# denary-cell-v1.net
KiCad netlist of a schematic drawn in EAGLE
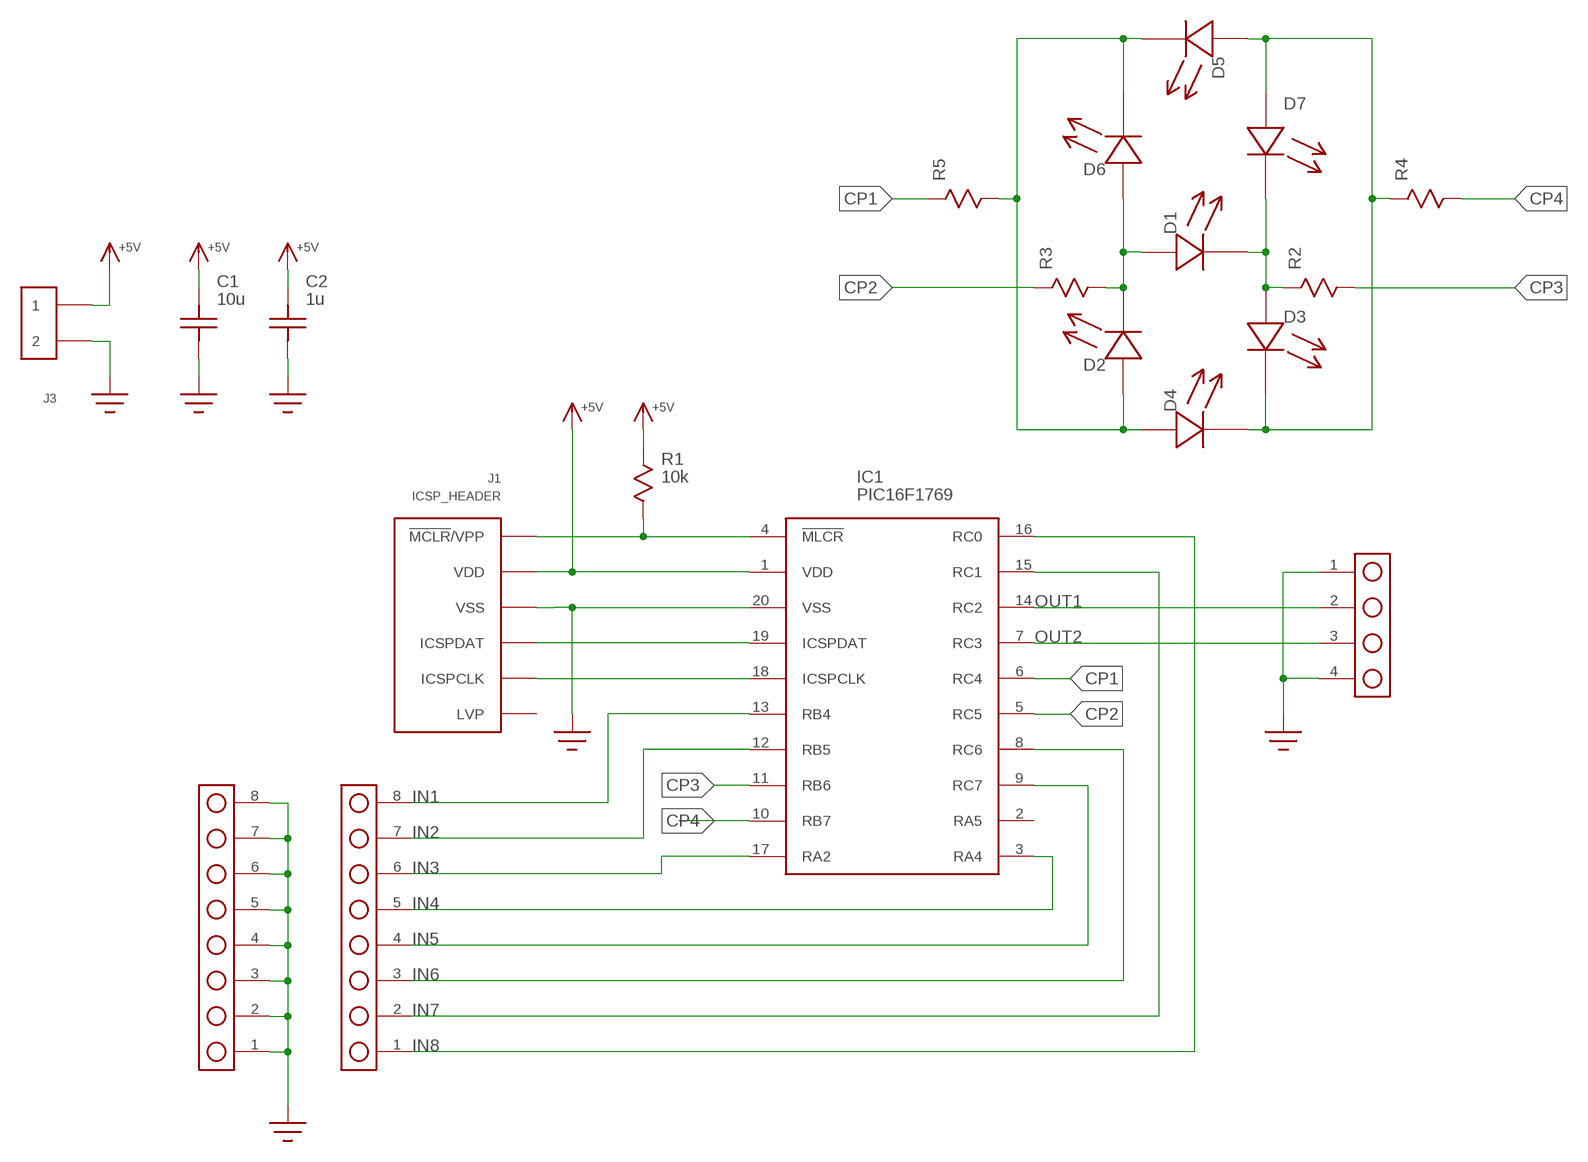
[diagram p0: schematic, sheet 1]

(export (version "E")
  (design (tool "Eeschema 10.0.6"))
  (components
    (comp (ref "C1")
      (value "10u")
      (footprint "eagle-import:1206")
      (libsource (lib "eagle-import") (part "C1206"))
    )
    (comp (ref "C2")
      (value "1u")
      (footprint "eagle-import:C0603")
      (libsource (lib "eagle-import") (part "C0603"))
    )
    (comp (ref "D1")
      (value "LED")
      (footprint "eagle-import:LED_0603")
      (libsource (lib "eagle-import") (part "LED"))
    )
    (comp (ref "D2")
      (value "LED")
      (footprint "eagle-import:LED_0603")
      (libsource (lib "eagle-import") (part "LED"))
    )
    (comp (ref "D3")
      (value "LED")
      (footprint "eagle-import:LED_0603")
      (libsource (lib "eagle-import") (part "LED"))
    )
    (comp (ref "D4")
      (value "LED")
      (footprint "eagle-import:LED_0603")
      (libsource (lib "eagle-import") (part "LED"))
    )
    (comp (ref "D5")
      (value "LED")
      (footprint "eagle-import:LED_0603")
      (libsource (lib "eagle-import") (part "LED"))
    )
    (comp (ref "D6")
      (value "LED")
      (footprint "eagle-import:LED_0603")
      (libsource (lib "eagle-import") (part "LED"))
    )
    (comp (ref "D7")
      (value "LED")
      (footprint "eagle-import:LED_0603")
      (libsource (lib "eagle-import") (part "LED"))
    )
    (comp (ref "IC1")
      (value "PIC16F1769")
      (footprint "eagle-import:SOIC-20W")
      (libsource (lib "eagle-import") (part "PIC16F1769"))
    )
    (comp (ref "J1")
      (value "ICSP_HEADER")
      (footprint "eagle-import:HEADER_6PIN")
      (libsource (lib "eagle-import") (part "ICSP_HEADER"))
    )
    (comp (ref "J2")
      (value "HEADER_4PIN")
      (footprint "eagle-import:HEADER_4PIN")
      (libsource (lib "eagle-import") (part "HEADER_4PIN"))
    )
    (comp (ref "J3")
      (value "HEADER_2PIN")
      (footprint "eagle-import:HEADER_2PIN")
      (libsource (lib "eagle-import") (part "HEADER_2PIN"))
    )
    (comp (ref "J4")
      (value "HEADER_8PIN")
      (footprint "eagle-import:HEADER_8_PIN")
      (libsource (lib "eagle-import") (part "HEADER_8PIN"))
    )
    (comp (ref "J5")
      (value "HEADER_8PIN")
      (footprint "eagle-import:HEADER_8_PIN")
      (libsource (lib "eagle-import") (part "HEADER_8PIN"))
    )
    (comp (ref "R1")
      (value "10k")
      (footprint "eagle-import:R0603")
      (libsource (lib "eagle-import") (part "R0603"))
    )
    (comp (ref "R2")
      (value "R0603")
      (footprint "eagle-import:R0603")
      (libsource (lib "eagle-import") (part "R0603"))
    )
    (comp (ref "R3")
      (value "R0603")
      (footprint "eagle-import:R0603")
      (libsource (lib "eagle-import") (part "R0603"))
    )
    (comp (ref "R4")
      (value "R0603")
      (footprint "eagle-import:R0603")
      (libsource (lib "eagle-import") (part "R0603"))
    )
    (comp (ref "R5")
      (value "R0603")
      (footprint "eagle-import:R0603")
      (libsource (lib "eagle-import") (part "R0603"))
    )
  )
  (nets
    (net (code "1") (name "+5V") (class "Default")
      (node (ref "C1") (pin "P$2") (pinfunction "P$2_P$2") (pintype "bidirectional"))
      (node (ref "C2") (pin "P$2") (pinfunction "P$2_P$2") (pintype "bidirectional"))
      (node (ref "IC1") (pin "1") (pinfunction "VDD_1") (pintype "bidirectional"))
      (node (ref "J1") (pin "2") (pinfunction "VDD_2") (pintype "bidirectional"))
      (node (ref "J3") (pin "1") (pinfunction "1_1") (pintype "bidirectional"))
      (node (ref "R1") (pin "P$1") (pinfunction "P$3_P$1") (pintype "bidirectional"))
    )
    (net (code "2") (name "/IN1") (class "Default")
      (node (ref "IC1") (pin "13") (pinfunction "RB4_13") (pintype "bidirectional"))
      (node (ref "J4") (pin "8") (pinfunction "8_8") (pintype "bidirectional"))
    )
    (net (code "3") (name "/IN2") (class "Default")
      (node (ref "IC1") (pin "12") (pinfunction "RB5_12") (pintype "bidirectional"))
      (node (ref "J4") (pin "7") (pinfunction "7_7") (pintype "bidirectional"))
    )
    (net (code "4") (name "/IN3") (class "Default")
      (node (ref "IC1") (pin "17") (pinfunction "RA2_17") (pintype "bidirectional"))
      (node (ref "J4") (pin "6") (pinfunction "6_6") (pintype "bidirectional"))
    )
    (net (code "5") (name "/IN4") (class "Default")
      (node (ref "IC1") (pin "3") (pinfunction "RA4_3") (pintype "bidirectional"))
      (node (ref "J4") (pin "5") (pinfunction "5_5") (pintype "bidirectional"))
    )
    (net (code "6") (name "/IN5") (class "Default")
      (node (ref "IC1") (pin "9") (pinfunction "RC7_9") (pintype "bidirectional"))
      (node (ref "J4") (pin "4") (pinfunction "4_4") (pintype "bidirectional"))
    )
    (net (code "7") (name "/IN6") (class "Default")
      (node (ref "IC1") (pin "8") (pinfunction "RC6_8") (pintype "bidirectional"))
      (node (ref "J4") (pin "3") (pinfunction "3_3") (pintype "bidirectional"))
    )
    (net (code "8") (name "/IN7") (class "Default")
      (node (ref "IC1") (pin "15") (pinfunction "RC1_15") (pintype "bidirectional"))
      (node (ref "J4") (pin "2") (pinfunction "2_2") (pintype "bidirectional"))
    )
    (net (code "9") (name "/IN8") (class "Default")
      (node (ref "IC1") (pin "16") (pinfunction "RC0_16") (pintype "bidirectional"))
      (node (ref "J4") (pin "1") (pinfunction "1_1") (pintype "bidirectional"))
    )
    (net (code "10") (name "/OUT1") (class "Default")
      (node (ref "IC1") (pin "14") (pinfunction "RC2_14") (pintype "bidirectional"))
      (node (ref "J2") (pin "2") (pinfunction "2_2") (pintype "bidirectional"))
    )
    (net (code "11") (name "/OUT2") (class "Default")
      (node (ref "IC1") (pin "7") (pinfunction "RC3_7") (pintype "bidirectional"))
      (node (ref "J2") (pin "3") (pinfunction "3_3") (pintype "bidirectional"))
    )
    (net (code "12") (name "CP1") (class "Default")
      (node (ref "IC1") (pin "6") (pinfunction "RC4_6") (pintype "bidirectional"))
      (node (ref "R5") (pin "P$1") (pinfunction "P$3_P$1") (pintype "bidirectional"))
    )
    (net (code "13") (name "CP2") (class "Default")
      (node (ref "IC1") (pin "5") (pinfunction "RC5_5") (pintype "bidirectional"))
      (node (ref "R3") (pin "P$1") (pinfunction "P$3_P$1") (pintype "bidirectional"))
    )
    (net (code "14") (name "CP3") (class "Default")
      (node (ref "IC1") (pin "11") (pinfunction "RB6_11") (pintype "bidirectional"))
      (node (ref "R2") (pin "P$2") (pinfunction "P$4_P$2") (pintype "bidirectional"))
    )
    (net (code "15") (name "CP4") (class "Default")
      (node (ref "IC1") (pin "10") (pinfunction "RB7_10") (pintype "bidirectional"))
      (node (ref "R4") (pin "P$2") (pinfunction "P$4_P$2") (pintype "bidirectional"))
    )
    (net (code "16") (name "GND") (class "Default")
      (node (ref "C1") (pin "P$1") (pinfunction "P$1_P$1") (pintype "bidirectional"))
      (node (ref "C2") (pin "P$1") (pinfunction "P$1_P$1") (pintype "bidirectional"))
      (node (ref "IC1") (pin "20") (pinfunction "VSS_20") (pintype "bidirectional"))
      (node (ref "J1") (pin "3") (pinfunction "VSS_3") (pintype "bidirectional"))
      (node (ref "J2") (pin "1") (pinfunction "1_1") (pintype "bidirectional"))
      (node (ref "J2") (pin "4") (pinfunction "4_4") (pintype "bidirectional"))
      (node (ref "J3") (pin "2") (pinfunction "2_2") (pintype "bidirectional"))
      (node (ref "J5") (pin "1") (pinfunction "1_1") (pintype "bidirectional"))
      (node (ref "J5") (pin "2") (pinfunction "2_2") (pintype "bidirectional"))
      (node (ref "J5") (pin "3") (pinfunction "3_3") (pintype "bidirectional"))
      (node (ref "J5") (pin "4") (pinfunction "4_4") (pintype "bidirectional"))
      (node (ref "J5") (pin "5") (pinfunction "5_5") (pintype "bidirectional"))
      (node (ref "J5") (pin "6") (pinfunction "6_6") (pintype "bidirectional"))
      (node (ref "J5") (pin "7") (pinfunction "7_7") (pintype "bidirectional"))
      (node (ref "J5") (pin "8") (pinfunction "8_8") (pintype "bidirectional"))
    )
    (net (code "17") (name "Net-(IC1-ICSPCLK)") (class "Default")
      (node (ref "IC1") (pin "18") (pinfunction "ICSPCLK_18") (pintype "bidirectional"))
      (node (ref "J1") (pin "5") (pinfunction "ICSPCLK_5") (pintype "bidirectional"))
    )
    (net (code "18") (name "Net-(IC1-ICSPDAT)") (class "Default")
      (node (ref "IC1") (pin "19") (pinfunction "ICSPDAT_19") (pintype "bidirectional"))
      (node (ref "J1") (pin "4") (pinfunction "ICSPDAT_4") (pintype "bidirectional"))
    )
    (net (code "19") (name "Net-(IC1-~{MLCR})") (class "Default")
      (node (ref "IC1") (pin "4") (pinfunction "~{MLCR}_4") (pintype "bidirectional"))
      (node (ref "J1") (pin "1") (pinfunction "~{MCLR}/VPP_1") (pintype "bidirectional"))
      (node (ref "R1") (pin "P$2") (pinfunction "P$4_P$2") (pintype "bidirectional"))
    )
    (net (code "20") (name "Net-(R2-P$3)") (class "Default")
      (node (ref "D1") (pin "C") (pinfunction "C_C") (pintype "bidirectional"))
      (node (ref "D3") (pin "A") (pinfunction "A_A") (pintype "bidirectional"))
      (node (ref "D7") (pin "C") (pinfunction "C_C") (pintype "bidirectional"))
      (node (ref "R2") (pin "P$1") (pinfunction "P$3_P$1") (pintype "bidirectional"))
    )
    (net (code "21") (name "Net-(R3-P$4)") (class "Default")
      (node (ref "D1") (pin "A") (pinfunction "A_A") (pintype "bidirectional"))
      (node (ref "D2") (pin "C") (pinfunction "C_C") (pintype "bidirectional"))
      (node (ref "D6") (pin "A") (pinfunction "A_A") (pintype "bidirectional"))
      (node (ref "R3") (pin "P$2") (pinfunction "P$4_P$2") (pintype "bidirectional"))
    )
    (net (code "22") (name "Net-(R4-P$3)") (class "Default")
      (node (ref "D3") (pin "C") (pinfunction "C_C") (pintype "bidirectional"))
      (node (ref "D4") (pin "C") (pinfunction "C_C") (pintype "bidirectional"))
      (node (ref "D5") (pin "A") (pinfunction "A_A") (pintype "bidirectional"))
      (node (ref "D7") (pin "A") (pinfunction "A_A") (pintype "bidirectional"))
      (node (ref "R4") (pin "P$1") (pinfunction "P$3_P$1") (pintype "bidirectional"))
    )
    (net (code "23") (name "Net-(R5-P$4)") (class "Default")
      (node (ref "D2") (pin "A") (pinfunction "A_A") (pintype "bidirectional"))
      (node (ref "D4") (pin "A") (pinfunction "A_A") (pintype "bidirectional"))
      (node (ref "D5") (pin "C") (pinfunction "C_C") (pintype "bidirectional"))
      (node (ref "D6") (pin "C") (pinfunction "C_C") (pintype "bidirectional"))
      (node (ref "R5") (pin "P$2") (pinfunction "P$4_P$2") (pintype "bidirectional"))
    )
    (net (code "24") (name "unconnected-(IC1-RA5-Pad2)") (class "Default")
      (node (ref "IC1") (pin "2") (pinfunction "RA5_2") (pintype "bidirectional"))
    )
    (net (code "25") (name "unconnected-(J1-LVP-Pad6)") (class "Default")
      (node (ref "J1") (pin "6") (pinfunction "LVP_6") (pintype "bidirectional"))
    )
  )
)
